# MinimumSistem.net
KiCad netlist of a schematic drawn in EAGLE
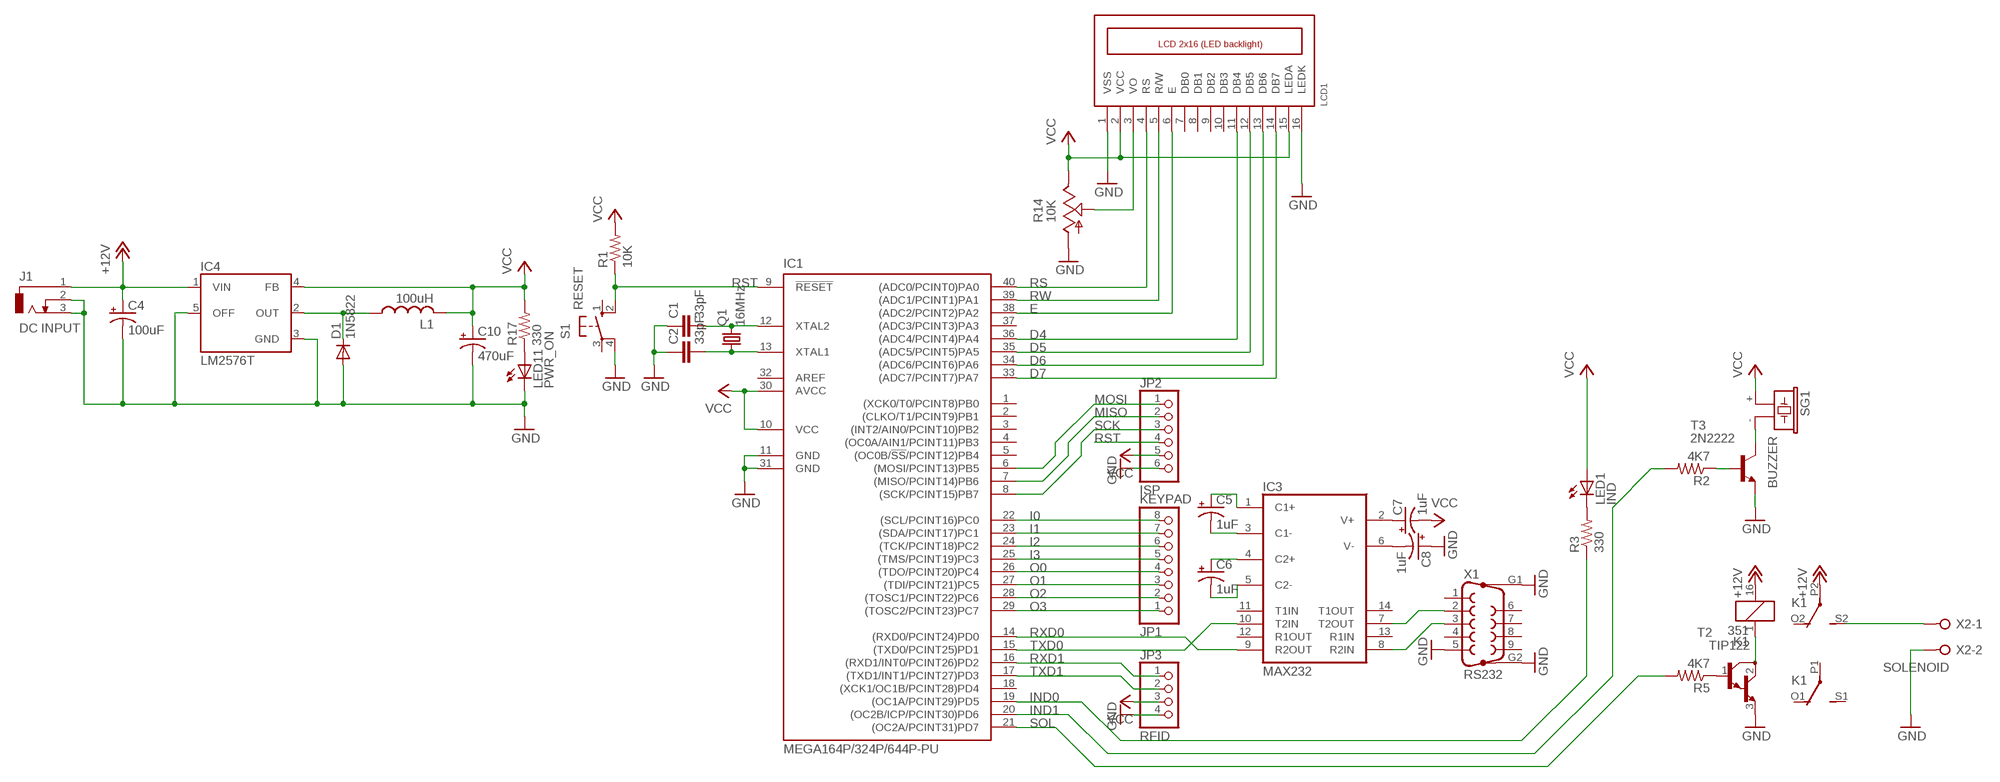
[diagram p0: schematic, sheet 1]

(export (version "E")
  (design (tool "Eeschema 10.0.6"))
  (components
    (comp (ref "C1")
      (value "33pF")
      (footprint "eagle-import:C025-024X044")
      (libsource (lib "eagle-import") (part "C-EU025-024X044"))
    )
    (comp (ref "C2")
      (value "33pF")
      (footprint "eagle-import:C025-024X044")
      (libsource (lib "eagle-import") (part "C-EU025-024X044"))
    )
    (comp (ref "C4")
      (value "100uF")
      (footprint "eagle-import:E2,5-6")
      (libsource (lib "eagle-import") (part "CPOL-USE2.5-6"))
    )
    (comp (ref "C5")
      (value "1uF")
      (footprint "eagle-import:E2-4")
      (libsource (lib "eagle-import") (part "CPOL-USE2-4"))
    )
    (comp (ref "C6")
      (value "1uF")
      (footprint "eagle-import:E2-4")
      (libsource (lib "eagle-import") (part "CPOL-USE2-4"))
    )
    (comp (ref "C7")
      (value "1uF")
      (footprint "eagle-import:E2-4")
      (libsource (lib "eagle-import") (part "CPOL-USE2-4"))
    )
    (comp (ref "C8")
      (value "1uF")
      (footprint "eagle-import:E2-4")
      (libsource (lib "eagle-import") (part "CPOL-USE2-4"))
    )
    (comp (ref "C10")
      (value "470uF")
      (footprint "eagle-import:E3,5-8")
      (libsource (lib "eagle-import") (part "CPOL-USE3.5-8"))
    )
    (comp (ref "D1")
      (value "1N5822")
      (footprint "eagle-import:DO201-15")
      (libsource (lib "eagle-import") (part "1N5400"))
    )
    (comp (ref "IC1")
      (value "MEGA164P/324P/644P-PU")
      (footprint "eagle-import:DIL40")
      (libsource (lib "eagle-import") (part "MEGA164P/324P/644P-PU"))
    )
    (comp (ref "IC3")
      (value "MAX232")
      (footprint "eagle-import:DIL16")
      (fields (field (name "MF") "MAXIM") (field (name "MPN") "MAX232ACPE+"))
      (libsource (lib "eagle-import") (part "MAX232"))
    )
    (comp (ref "IC4")
      (value "LM2576T")
      (footprint "eagle-import:TO220-5")
      (libsource (lib "eagle-import") (part "LM2576T"))
    )
    (comp (ref "J1")
      (value "DC INPUT")
      (footprint "eagle-import:DCJ0202")
      (libsource (lib "eagle-import") (part "DCJ0202"))
    )
    (comp (ref "JP1")
      (value "KEYPAD")
      (footprint "eagle-import:1X08_90")
      (libsource (lib "eagle-import") (part "PINHD-1X8/90"))
    )
    (comp (ref "JP2")
      (value "ISP")
      (footprint "eagle-import:1X06")
      (libsource (lib "eagle-import") (part "PINHD-1X6"))
    )
    (comp (ref "JP3")
      (value "RFID")
      (footprint "eagle-import:1X04")
      (libsource (lib "eagle-import") (part "PINHD-1X4"))
    )
    (comp (ref "K1")
      (value "351")
      (footprint "eagle-import:351")
      (libsource (lib "eagle-import") (part "351"))
    )
    (comp (ref "L1")
      (value "100uH")
      (footprint "eagle-import:TJ3-U2")
      (libsource (lib "eagle-import") (part "L-USTJ3-U2"))
    )
    (comp (ref "LCD1")
      (value "LCD_2X16")
      (footprint "eagle-import:HY-1602F")
      (libsource (lib "eagle-import") (part "LCD_2X16_SIL"))
    )
    (comp (ref "LED1")
      (value "IND")
      (footprint "eagle-import:LED5MM")
      (libsource (lib "eagle-import") (part "LED5MM"))
    )
    (comp (ref "LED11")
      (value "PWR_ON")
      (footprint "eagle-import:LED3MM")
      (libsource (lib "eagle-import") (part "LED3MM"))
    )
    (comp (ref "Q1")
      (value "16MHz")
      (footprint "eagle-import:HC49_S")
      (libsource (lib "eagle-import") (part "CRYSTALHC49S"))
    )
    (comp (ref "R1")
      (value "10K")
      (footprint "eagle-import:0207_10")
      (libsource (lib "eagle-import") (part "R-US_0207/10"))
    )
    (comp (ref "R2")
      (value "4K7")
      (footprint "eagle-import:0207_10")
      (libsource (lib "eagle-import") (part "R-US_0207/10"))
    )
    (comp (ref "R3")
      (value "330")
      (footprint "eagle-import:0207_10")
      (libsource (lib "eagle-import") (part "R-US_0207/10"))
    )
    (comp (ref "R5")
      (value "4K7")
      (footprint "eagle-import:0207_10")
      (libsource (lib "eagle-import") (part "R-US_0207/10"))
    )
    (comp (ref "R14")
      (value "10K")
      (footprint "eagle-import:CA6V")
      (libsource (lib "eagle-import") (part "TRIM_US-CA6V"))
    )
    (comp (ref "R17")
      (value "330")
      (footprint "eagle-import:0207_10")
      (libsource (lib "eagle-import") (part "R-US_0207/10"))
    )
    (comp (ref "S1")
      (value "RESET")
      (footprint "eagle-import:B3F-10XX")
      (fields (field (name "MPN") "B3F-1000"))
      (libsource (lib "eagle-import") (part "10-XX"))
    )
    (comp (ref "SG1")
      (value "BUZZER")
      (footprint "eagle-import:F_CM12P")
      (libsource (lib "eagle-import") (part "F/CM12P"))
    )
    (comp (ref "T2")
      (value "TIP122")
      (footprint "eagle-import:TO220")
      (libsource (lib "eagle-import") (part "TIP122"))
    )
    (comp (ref "T3")
      (value "2N2222")
      (footprint "eagle-import:TO92-EBC-OVAL")
      (libsource (lib "eagle-import") (part "2N2222"))
    )
    (comp (ref "X1")
      (value "RS232")
      (footprint "eagle-import:F09HP")
      (libsource (lib "eagle-import") (part "F09HP"))
    )
    (comp (ref "X2")
      (value "SOLENOID")
      (footprint "eagle-import:W237-132")
      (libsource (lib "eagle-import") (part "W237-02P"))
    )
  )
  (nets
    (net (code "1") (name "+12V") (class "Default")
      (node (ref "C4") (pin "+") (pinfunction "+_+") (pintype "passive"))
      (node (ref "IC4") (pin "1") (pinfunction "VIN_1") (pintype "power_in"))
      (node (ref "J1") (pin "1") (pinfunction "1_1") (pintype "passive"))
      (node (ref "K1") (pin "16") (pinfunction "2_16") (pintype "passive"))
      (node (ref "K1") (pin "P2") (pinfunction "P_P2") (pintype "passive"))
    )
    (net (code "2") (name "/AREF") (class "Default")
      (node (ref "IC1") (pin "32") (pinfunction "AREF_32") (pintype "power_in"))
    )
    (net (code "3") (name "/D4") (class "Default")
      (node (ref "IC1") (pin "36") (pinfunction "(ADC4/PCINT4)PA4_36") (pintype "bidirectional"))
      (node (ref "LCD1") (pin "11") (pinfunction "DB4_11") (pintype "bidirectional"))
    )
    (net (code "4") (name "/D5") (class "Default")
      (node (ref "IC1") (pin "35") (pinfunction "(ADC5/PCINT5)PA5_35") (pintype "bidirectional"))
      (node (ref "LCD1") (pin "12") (pinfunction "DB5_12") (pintype "bidirectional"))
    )
    (net (code "5") (name "/D6") (class "Default")
      (node (ref "IC1") (pin "34") (pinfunction "(ADC6/PCINT6)PA6_34") (pintype "bidirectional"))
      (node (ref "LCD1") (pin "13") (pinfunction "DB6_13") (pintype "bidirectional"))
    )
    (net (code "6") (name "/D7") (class "Default")
      (node (ref "IC1") (pin "33") (pinfunction "(ADC7/PCINT7)PA7_33") (pintype "bidirectional"))
      (node (ref "LCD1") (pin "14") (pinfunction "DB7_14") (pintype "bidirectional"))
    )
    (net (code "7") (name "/E") (class "Default")
      (node (ref "IC1") (pin "38") (pinfunction "(ADC2/PCINT2)PA2_38") (pintype "bidirectional"))
      (node (ref "LCD1") (pin "6") (pinfunction "E_6") (pintype "input"))
    )
    (net (code "8") (name "/I0") (class "Default")
      (node (ref "IC1") (pin "22") (pinfunction "(SCL/PCINT16)PC0_22") (pintype "bidirectional"))
      (node (ref "JP1") (pin "8") (pinfunction "8_8") (pintype "passive"))
    )
    (net (code "9") (name "/I1") (class "Default")
      (node (ref "IC1") (pin "23") (pinfunction "(SDA/PCINT17)PC1_23") (pintype "bidirectional"))
      (node (ref "JP1") (pin "7") (pinfunction "7_7") (pintype "passive"))
    )
    (net (code "10") (name "/I2") (class "Default")
      (node (ref "IC1") (pin "24") (pinfunction "(TCK/PCINT18)PC2_24") (pintype "bidirectional"))
      (node (ref "JP1") (pin "6") (pinfunction "6_6") (pintype "passive"))
    )
    (net (code "11") (name "/I3") (class "Default")
      (node (ref "IC1") (pin "25") (pinfunction "(TMS/PCINT19)PC3_25") (pintype "bidirectional"))
      (node (ref "JP1") (pin "5") (pinfunction "5_5") (pintype "passive"))
    )
    (net (code "12") (name "/IND0") (class "Default")
      (node (ref "IC1") (pin "19") (pinfunction "(OC1A/PCINT29)PD5_19") (pintype "bidirectional"))
      (node (ref "R3") (pin "1") (pinfunction "1_1") (pintype "passive"))
    )
    (net (code "13") (name "/IND1") (class "Default")
      (node (ref "IC1") (pin "20") (pinfunction "(OC2B/ICP/PCINT30)PD6_20") (pintype "bidirectional"))
      (node (ref "R2") (pin "2") (pinfunction "2_2") (pintype "passive"))
    )
    (net (code "14") (name "/MISO") (class "Default")
      (node (ref "IC1") (pin "7") (pinfunction "(MISO/PCINT14)PB6_7") (pintype "bidirectional"))
      (node (ref "JP2") (pin "2") (pinfunction "2_2") (pintype "passive"))
    )
    (net (code "15") (name "/MOSI") (class "Default")
      (node (ref "IC1") (pin "6") (pinfunction "(MOSI/PCINT13)PB5_6") (pintype "bidirectional"))
      (node (ref "JP2") (pin "1") (pinfunction "1_1") (pintype "passive"))
    )
    (net (code "16") (name "/O0") (class "Default")
      (node (ref "IC1") (pin "26") (pinfunction "(TDO/PCINT20)PC4_26") (pintype "bidirectional"))
      (node (ref "JP1") (pin "4") (pinfunction "4_4") (pintype "passive"))
    )
    (net (code "17") (name "/O1") (class "Default")
      (node (ref "IC1") (pin "27") (pinfunction "(TDI/PCINT21)PC5_27") (pintype "bidirectional"))
      (node (ref "JP1") (pin "3") (pinfunction "3_3") (pintype "passive"))
    )
    (net (code "18") (name "/O2") (class "Default")
      (node (ref "IC1") (pin "28") (pinfunction "(TOSC1/PCINT22)PC6_28") (pintype "bidirectional"))
      (node (ref "JP1") (pin "2") (pinfunction "2_2") (pintype "passive"))
    )
    (net (code "19") (name "/O3") (class "Default")
      (node (ref "IC1") (pin "29") (pinfunction "(TOSC2/PCINT23)PC7_29") (pintype "bidirectional"))
      (node (ref "JP1") (pin "1") (pinfunction "1_1") (pintype "passive"))
    )
    (net (code "20") (name "/RS") (class "Default")
      (node (ref "IC1") (pin "40") (pinfunction "(ADC0/PCINT0)PA0_40") (pintype "bidirectional"))
      (node (ref "LCD1") (pin "4") (pinfunction "RS_4") (pintype "input"))
    )
    (net (code "21") (name "/RST") (class "Default")
      (node (ref "IC1") (pin "9") (pinfunction "~{RESET}_9") (pintype "input"))
      (node (ref "JP2") (pin "4") (pinfunction "4_4") (pintype "passive"))
      (node (ref "R1") (pin "1") (pinfunction "1_1") (pintype "passive"))
      (node (ref "S1") (pin "2") (pinfunction "S1_2") (pintype "passive"))
    )
    (net (code "22") (name "/RW") (class "Default")
      (node (ref "IC1") (pin "39") (pinfunction "(ADC1/PCINT1)PA1_39") (pintype "bidirectional"))
      (node (ref "LCD1") (pin "5") (pinfunction "R/W_5") (pintype "input"))
    )
    (net (code "23") (name "/RXD0") (class "Default")
      (node (ref "IC1") (pin "14") (pinfunction "(RXD0/PCINT24)PD0_14") (pintype "bidirectional"))
      (node (ref "IC3") (pin "9") (pinfunction "R2OUT_9") (pintype "output"))
    )
    (net (code "24") (name "/RXD1") (class "Default")
      (node (ref "IC1") (pin "16") (pinfunction "(RXD1/INT0/PCINT26)PD2_16") (pintype "bidirectional"))
      (node (ref "JP3") (pin "1") (pinfunction "1_1") (pintype "passive"))
    )
    (net (code "25") (name "/SCK") (class "Default")
      (node (ref "IC1") (pin "8") (pinfunction "(SCK/PCINT15)PB7_8") (pintype "bidirectional"))
      (node (ref "JP2") (pin "3") (pinfunction "3_3") (pintype "passive"))
    )
    (net (code "26") (name "/SOL") (class "Default")
      (node (ref "IC1") (pin "21") (pinfunction "(OC2A/PCINT31)PD7_21") (pintype "bidirectional"))
      (node (ref "R5") (pin "2") (pinfunction "2_2") (pintype "passive"))
    )
    (net (code "27") (name "/TXD0") (class "Default")
      (node (ref "IC1") (pin "15") (pinfunction "(TXD0/PCINT25)PD1_15") (pintype "bidirectional"))
      (node (ref "IC3") (pin "10") (pinfunction "T2IN_10") (pintype "input"))
    )
    (net (code "28") (name "/TXD1") (class "Default")
      (node (ref "IC1") (pin "17") (pinfunction "(TXD1/INT1/PCINT27)PD3_17") (pintype "bidirectional"))
      (node (ref "JP3") (pin "2") (pinfunction "2_2") (pintype "passive"))
    )
    (net (code "29") (name "GND") (class "Default")
      (node (ref "C1") (pin "1") (pinfunction "1_1") (pintype "passive"))
      (node (ref "C10") (pin "-") (pinfunction "-_-") (pintype "passive"))
      (node (ref "C2") (pin "1") (pinfunction "1_1") (pintype "passive"))
      (node (ref "C4") (pin "-") (pinfunction "-_-") (pintype "passive"))
      (node (ref "C8") (pin "+") (pinfunction "+_+") (pintype "passive"))
      (node (ref "D1") (pin "A") (pinfunction "A_A") (pintype "passive"))
      (node (ref "IC1") (pin "11") (pinfunction "GND_11") (pintype "power_in"))
      (node (ref "IC1") (pin "31") (pinfunction "GND_31") (pintype "power_in"))
      (node (ref "IC4") (pin "3") (pinfunction "GND_3") (pintype "power_in"))
      (node (ref "IC4") (pin "5") (pinfunction "OFF_5") (pintype "input"))
      (node (ref "J1") (pin "2") (pinfunction "2_2") (pintype "passive"))
      (node (ref "J1") (pin "3") (pinfunction "3_3") (pintype "passive"))
      (node (ref "JP2") (pin "6") (pinfunction "6_6") (pintype "passive"))
      (node (ref "JP3") (pin "4") (pinfunction "4_4") (pintype "passive"))
      (node (ref "LCD1") (pin "1") (pinfunction "VSS_1") (pintype "power_in"))
      (node (ref "LCD1") (pin "16") (pinfunction "LEDK_16") (pintype "passive"))
      (node (ref "LED11") (pin "K") (pinfunction "C_K") (pintype "passive"))
      (node (ref "R14") (pin "A") (pinfunction "A_A") (pintype "passive"))
      (node (ref "S1") (pin "4") (pinfunction "P1_4") (pintype "passive"))
      (node (ref "T2") (pin "3") (pinfunction "E_3") (pintype "passive"))
      (node (ref "T3") (pin "E") (pinfunction "E_E") (pintype "passive"))
      (node (ref "X1") (pin "5") (pinfunction "5_5") (pintype "passive"))
      (node (ref "X1") (pin "G1") (pinfunction "G1_G1") (pintype "passive"))
      (node (ref "X1") (pin "G2") (pinfunction "G2_G2") (pintype "passive"))
      (node (ref "X2") (pin "2") (pinfunction "KL_2") (pintype "passive"))
    )
    (net (code "30") (name "Net-(IC1-XTAL1)") (class "Default")
      (node (ref "C2") (pin "2") (pinfunction "2_2") (pintype "passive"))
      (node (ref "IC1") (pin "13") (pinfunction "XTAL1_13") (pintype "input"))
      (node (ref "Q1") (pin "1") (pinfunction "1_1") (pintype "passive"))
    )
    (net (code "31") (name "Net-(IC1-XTAL2)") (class "Default")
      (node (ref "C1") (pin "2") (pinfunction "2_2") (pintype "passive"))
      (node (ref "IC1") (pin "12") (pinfunction "XTAL2_12") (pintype "output"))
      (node (ref "Q1") (pin "2") (pinfunction "2_2") (pintype "passive"))
    )
    (net (code "32") (name "Net-(IC3A-C1+)") (class "Default")
      (node (ref "C5") (pin "+") (pinfunction "+_+") (pintype "passive"))
      (node (ref "IC3") (pin "1") (pinfunction "C1+_1") (pintype "bidirectional"))
    )
    (net (code "33") (name "Net-(IC3A-C1-)") (class "Default")
      (node (ref "C5") (pin "-") (pinfunction "-_-") (pintype "passive"))
      (node (ref "IC3") (pin "3") (pinfunction "C1-_3") (pintype "bidirectional"))
    )
    (net (code "34") (name "Net-(IC3A-C2+)") (class "Default")
      (node (ref "C6") (pin "+") (pinfunction "+_+") (pintype "passive"))
      (node (ref "IC3") (pin "4") (pinfunction "C2+_4") (pintype "bidirectional"))
    )
    (net (code "35") (name "Net-(IC3A-C2-)") (class "Default")
      (node (ref "C6") (pin "-") (pinfunction "-_-") (pintype "passive"))
      (node (ref "IC3") (pin "5") (pinfunction "C2-_5") (pintype "bidirectional"))
    )
    (net (code "36") (name "Net-(IC3A-R2IN)") (class "Default")
      (node (ref "IC3") (pin "8") (pinfunction "R2IN_8") (pintype "input"))
      (node (ref "X1") (pin "3") (pinfunction "3_3") (pintype "passive"))
    )
    (net (code "37") (name "Net-(IC3A-T2OUT)") (class "Default")
      (node (ref "IC3") (pin "7") (pinfunction "T2OUT_7") (pintype "output"))
      (node (ref "X1") (pin "2") (pinfunction "2_2") (pintype "passive"))
    )
    (net (code "38") (name "Net-(IC3A-V+)") (class "Default")
      (node (ref "C7") (pin "+") (pinfunction "+_+") (pintype "passive"))
      (node (ref "IC3") (pin "2") (pinfunction "V+_2") (pintype "bidirectional"))
    )
    (net (code "39") (name "Net-(IC3A-V-)") (class "Default")
      (node (ref "C8") (pin "-") (pinfunction "-_-") (pintype "passive"))
      (node (ref "IC3") (pin "6") (pinfunction "V-_6") (pintype "bidirectional"))
    )
    (net (code "40") (name "Net-(IC4-OUT)") (class "Default")
      (node (ref "D1") (pin "C") (pinfunction "C_C") (pintype "passive"))
      (node (ref "IC4") (pin "2") (pinfunction "OUT_2") (pintype "output"))
      (node (ref "L1") (pin "1") (pinfunction "1_1") (pintype "passive"))
    )
    (net (code "41") (name "Net-(K1C-S)") (class "Default")
      (node (ref "K1") (pin "S2") (pinfunction "S_S2") (pintype "passive"))
      (node (ref "X2") (pin "1") (pinfunction "KL_1") (pintype "passive"))
    )
    (net (code "42") (name "Net-(LCD1-VO)") (class "Default")
      (node (ref "LCD1") (pin "3") (pinfunction "VO_3") (pintype "input"))
      (node (ref "R14") (pin "S") (pinfunction "S_S") (pintype "passive"))
    )
    (net (code "43") (name "Net-(LED1-C)") (class "Default")
      (node (ref "LED1") (pin "K") (pinfunction "C_K") (pintype "passive"))
      (node (ref "R3") (pin "2") (pinfunction "2_2") (pintype "passive"))
    )
    (net (code "44") (name "Net-(LED11-PadA)") (class "Default")
      (node (ref "LED11") (pin "A") (pinfunction "A_A") (pintype "passive"))
      (node (ref "R17") (pin "1") (pinfunction "1_1") (pintype "passive"))
    )
    (net (code "45") (name "Net-(R2-Pad1)") (class "Default")
      (node (ref "R2") (pin "1") (pinfunction "1_1") (pintype "passive"))
      (node (ref "T3") (pin "B") (pinfunction "B_B") (pintype "passive"))
    )
    (net (code "46") (name "Net-(SG1-2)") (class "Default")
      (node (ref "SG1") (pin "-") (pinfunction "2_-") (pintype "passive"))
      (node (ref "T3") (pin "C") (pinfunction "C_C") (pintype "passive"))
    )
    (net (code "47") (name "Net-(T2-B)") (class "Default")
      (node (ref "R5") (pin "1") (pinfunction "1_1") (pintype "passive"))
      (node (ref "T2") (pin "1") (pinfunction "B_1") (pintype "passive"))
    )
    (net (code "48") (name "Net-(T2-C)") (class "Default")
      (node (ref "K1") (pin "1") (pinfunction "1_1") (pintype "passive"))
      (node (ref "T2") (pin "2") (pinfunction "C_2") (pintype "passive"))
    )
    (net (code "49") (name "VCC") (class "Default")
      (node (ref "C10") (pin "+") (pinfunction "+_+") (pintype "passive"))
      (node (ref "C7") (pin "-") (pinfunction "-_-") (pintype "passive"))
      (node (ref "IC1") (pin "10") (pinfunction "VCC_10") (pintype "power_in"))
      (node (ref "IC1") (pin "30") (pinfunction "AVCC_30") (pintype "power_in"))
      (node (ref "IC4") (pin "4") (pinfunction "FB_4") (pintype "input"))
      (node (ref "JP2") (pin "5") (pinfunction "5_5") (pintype "passive"))
      (node (ref "JP3") (pin "3") (pinfunction "3_3") (pintype "passive"))
      (node (ref "L1") (pin "2") (pinfunction "2_2") (pintype "passive"))
      (node (ref "LCD1") (pin "15") (pinfunction "LEDA_15") (pintype "passive"))
      (node (ref "LCD1") (pin "2") (pinfunction "VCC_2") (pintype "power_in"))
      (node (ref "LED1") (pin "A") (pinfunction "A_A") (pintype "passive"))
      (node (ref "R1") (pin "2") (pinfunction "2_2") (pintype "passive"))
      (node (ref "R14") (pin "E") (pinfunction "E_E") (pintype "passive"))
      (node (ref "R17") (pin "2") (pinfunction "2_2") (pintype "passive"))
      (node (ref "SG1") (pin "+") (pinfunction "1_+") (pintype "passive"))
    )
    (net (code "50") (name "unconnected-(IC1-(ADC3{slash}PCINT3)PA3-Pad37)") (class "Default")
      (node (ref "IC1") (pin "37") (pinfunction "(ADC3/PCINT3)PA3_37") (pintype "bidirectional"))
    )
    (net (code "51") (name "unconnected-(IC1-(CLKO{slash}T1{slash}PCINT9)PB1-Pad2)") (class "Default")
      (node (ref "IC1") (pin "2") (pinfunction "(CLKO/T1/PCINT9)PB1_2") (pintype "bidirectional"))
    )
    (net (code "52") (name "unconnected-(IC1-(INT2{slash}AIN0{slash}PCINT10)PB2-Pad3)") (class "Default")
      (node (ref "IC1") (pin "3") (pinfunction "(INT2/AIN0/PCINT10)PB2_3") (pintype "bidirectional"))
    )
    (net (code "53") (name "unconnected-(IC1-(OC0A{slash}AIN1{slash}PCINT11)PB3-Pad4)") (class "Default")
      (node (ref "IC1") (pin "4") (pinfunction "(OC0A/AIN1/PCINT11)PB3_4") (pintype "bidirectional"))
    )
    (net (code "54") (name "unconnected-(IC1-(OC0B{slash}~{SS}{slash}PCINT12)PB4-Pad5)") (class "Default")
      (node (ref "IC1") (pin "5") (pinfunction "(OC0B/~{SS}/PCINT12)PB4_5") (pintype "bidirectional"))
    )
    (net (code "55") (name "unconnected-(IC1-(XCK0{slash}T0{slash}PCINT8)PB0-Pad1)") (class "Default")
      (node (ref "IC1") (pin "1") (pinfunction "(XCK0/T0/PCINT8)PB0_1") (pintype "bidirectional"))
    )
    (net (code "56") (name "unconnected-(IC1-(XCK1{slash}OC1B{slash}PCINT28)PD4-Pad18)") (class "Default")
      (node (ref "IC1") (pin "18") (pinfunction "(XCK1/OC1B/PCINT28)PD4_18") (pintype "bidirectional"))
    )
    (net (code "57") (name "unconnected-(IC3A-R1IN-Pad13)") (class "Default")
      (node (ref "IC3") (pin "13") (pinfunction "R1IN_13") (pintype "input"))
    )
    (net (code "58") (name "unconnected-(IC3A-R1OUT-Pad12)") (class "Default")
      (node (ref "IC3") (pin "12") (pinfunction "R1OUT_12") (pintype "output"))
    )
    (net (code "59") (name "unconnected-(IC3A-T1IN-Pad11)") (class "Default")
      (node (ref "IC3") (pin "11") (pinfunction "T1IN_11") (pintype "input"))
    )
    (net (code "60") (name "unconnected-(IC3A-T1OUT-Pad14)") (class "Default")
      (node (ref "IC3") (pin "14") (pinfunction "T1OUT_14") (pintype "output"))
    )
    (net (code "61") (name "unconnected-(K1B-O-PadO1)") (class "Default")
      (node (ref "K1") (pin "O1") (pinfunction "O_O1") (pintype "passive"))
    )
    (net (code "62") (name "unconnected-(K1B-P-PadP1)") (class "Default")
      (node (ref "K1") (pin "P1") (pinfunction "P_P1") (pintype "passive"))
    )
    (net (code "63") (name "unconnected-(K1B-S-PadS1)") (class "Default")
      (node (ref "K1") (pin "S1") (pinfunction "S_S1") (pintype "passive"))
    )
    (net (code "64") (name "unconnected-(K1C-O-PadO2)") (class "Default")
      (node (ref "K1") (pin "O2") (pinfunction "O_O2") (pintype "passive"))
    )
    (net (code "65") (name "unconnected-(LCD1-DB0-Pad7)") (class "Default")
      (node (ref "LCD1") (pin "7") (pinfunction "DB0_7") (pintype "bidirectional"))
    )
    (net (code "66") (name "unconnected-(LCD1-DB1-Pad8)") (class "Default")
      (node (ref "LCD1") (pin "8") (pinfunction "DB1_8") (pintype "bidirectional"))
    )
    (net (code "67") (name "unconnected-(LCD1-DB2-Pad9)") (class "Default")
      (node (ref "LCD1") (pin "9") (pinfunction "DB2_9") (pintype "bidirectional"))
    )
    (net (code "68") (name "unconnected-(LCD1-DB3-Pad10)") (class "Default")
      (node (ref "LCD1") (pin "10") (pinfunction "DB3_10") (pintype "bidirectional"))
    )
    (net (code "69") (name "unconnected-(S1-P-Pad3)") (class "Default")
      (node (ref "S1") (pin "3") (pinfunction "P_3") (pintype "passive"))
    )
    (net (code "70") (name "unconnected-(S1-S-Pad1)") (class "Default")
      (node (ref "S1") (pin "1") (pinfunction "S_1") (pintype "passive"))
    )
    (net (code "71") (name "unconnected-(X1-Pad1)") (class "Default")
      (node (ref "X1") (pin "1") (pinfunction "1_1") (pintype "passive"))
    )
    (net (code "72") (name "unconnected-(X1-Pad4)") (class "Default")
      (node (ref "X1") (pin "4") (pinfunction "4_4") (pintype "passive"))
    )
    (net (code "73") (name "unconnected-(X1-Pad6)") (class "Default")
      (node (ref "X1") (pin "6") (pinfunction "6_6") (pintype "passive"))
    )
    (net (code "74") (name "unconnected-(X1-Pad7)") (class "Default")
      (node (ref "X1") (pin "7") (pinfunction "7_7") (pintype "passive"))
    )
    (net (code "75") (name "unconnected-(X1-Pad8)") (class "Default")
      (node (ref "X1") (pin "8") (pinfunction "8_8") (pintype "passive"))
    )
    (net (code "76") (name "unconnected-(X1-Pad9)") (class "Default")
      (node (ref "X1") (pin "9") (pinfunction "9_9") (pintype "passive"))
    )
  )
)
